# design.net
KiCad netlist of a schematic drawn in Altium Designer
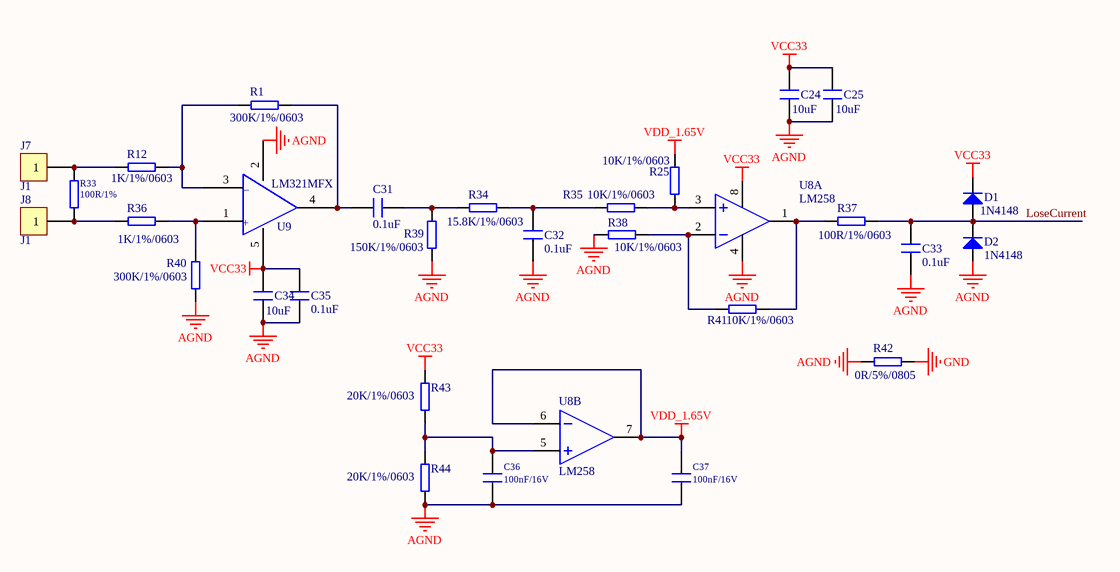
[diagram p0: 漏电流检测.SchDoc]

(export (version "E")
  (design (tool "Eeschema 10.0.6"))
  (components
    (comp (ref "C24") (value "10uF") (footprint "0603R") (libsource (lib "ES_Schematic") (part "CAP")))
    (comp (ref "C25") (value "10uF") (footprint "0603R") (libsource (lib "ES_Schematic") (part "CAP")))
    (comp (ref "C31") (value "0.1uF") (footprint "0603R") (libsource (lib "ES_Schematic") (part "CAP")))
    (comp (ref "C32") (value "0.1uF") (footprint "0603R") (libsource (lib "ES_Schematic") (part "CAP")))
    (comp (ref "C33") (value "0.1uF") (footprint "0603R") (libsource (lib "ES_Schematic") (part "CAP")))
    (comp (ref "C34") (value "10uF") (footprint "0603R") (libsource (lib "ES_Schematic") (part "CAP")))
    (comp (ref "C35") (value "0.1uF") (footprint "0603R") (libsource (lib "ES_Schematic") (part "CAP")))
    (comp (ref "C36") (value "100nF/16V") (footprint "0603R") (libsource (lib "ES_Schematic") (part "CAP")))
    (comp (ref "C37") (value "100nF/16V") (footprint "0603R") (libsource (lib "ES_Schematic") (part "CAP")))
    (comp (ref "D1") (value "1N4148") (footprint "1206D") (libsource (lib "ES_Schematic") (part "DIODE")))
    (comp (ref "D2") (value "1N4148") (footprint "1206D") (libsource (lib "ES_Schematic") (part "DIODE")))
    (comp (ref "J7") (value "J1") (footprint "贴片焊盘V1（3*2椭圆）") (libsource (lib "ES_Schematic") (part "J1")))
    (comp (ref "J8") (value "J1") (footprint "贴片焊盘V1（3*2椭圆）") (libsource (lib "ES_Schematic") (part "J1")))
    (comp (ref "R1") (value "300K/1%/0603") (footprint "0603r") (libsource (lib "ES_Schematic") (part "RES")))
    (comp (ref "R12") (value "1K/1%/0603") (footprint "0603r") (libsource (lib "ES_Schematic") (part "RES")))
    (comp (ref "R25") (value "10K/1%/0603") (footprint "0603r") (libsource (lib "ES_Schematic") (part "RES")))
    (comp (ref "R33") (value "100R/1%") (footprint "0805R") (libsource (lib "ES_Schematic") (part "RES")))
    (comp (ref "R34")
      (value "15.8K/1%/0603")
      (footprint "0603r")
      (libsource (lib "ES_Schematic") (part "RES"))
    )
    (comp (ref "R35") (value "10K/1%/0603") (footprint "0603r") (libsource (lib "ES_Schematic") (part "RES")))
    (comp (ref "R36") (value "1K/1%/0603") (footprint "0603r") (libsource (lib "ES_Schematic") (part "RES")))
    (comp (ref "R37")
      (value "100R/1%/0603")
      (footprint "0603r")
      (libsource (lib "ES_Schematic") (part "RES"))
    )
    (comp (ref "R38") (value "10K/1%/0603") (footprint "0603r") (libsource (lib "ES_Schematic") (part "RES")))
    (comp (ref "R39")
      (value "150K/1%/0603")
      (footprint "0603r")
      (libsource (lib "ES_Schematic") (part "RES"))
    )
    (comp (ref "R40")
      (value "300K/1%/0603")
      (footprint "0603r")
      (libsource (lib "ES_Schematic") (part "RES"))
    )
    (comp (ref "R41") (value "10K/1%/0603") (footprint "0603r") (libsource (lib "ES_Schematic") (part "RES")))
    (comp (ref "R42") (value "0R/5%/0805") (footprint "0805R") (libsource (lib "ES_Schematic") (part "RES")))
    (comp (ref "R43") (value "20K/1%/0603") (footprint "0603r") (libsource (lib "ES_Schematic") (part "RES")))
    (comp (ref "R44") (value "20K/1%/0603") (footprint "0603r") (libsource (lib "ES_Schematic") (part "RES")))
    (comp (ref "U8") (value "LM258") (footprint "SO8") (libsource (lib "sangjian") (part "LM358")))
    (comp (ref "U9")
      (value "LM321MFX")
      (footprint "SOT-23-5")
      (libsource (lib "ES_Schematic") (part "LM321MFX"))
    )
  )
  (nets
    (net (code "1") (name "/LoseCurrent") (class "Default")
      (node (ref "C33") (pin "1") (pinfunction "1_1") (pintype "passive"))
      (node (ref "D1") (pin "2") (pinfunction "A_2") (pintype "passive"))
      (node (ref "D2") (pin "1") (pinfunction "K_1") (pintype "passive"))
      (node (ref "R37") (pin "1") (pinfunction "1_1") (pintype "passive"))
    )
    (net (code "2") (name "AGND") (class "Default")
      (node (ref "C24") (pin "1") (pinfunction "1_1") (pintype "passive"))
      (node (ref "C25") (pin "1") (pinfunction "1_1") (pintype "passive"))
      (node (ref "C32") (pin "2") (pinfunction "2_2") (pintype "passive"))
      (node (ref "C33") (pin "2") (pinfunction "2_2") (pintype "passive"))
      (node (ref "C34") (pin "1") (pinfunction "1_1") (pintype "passive"))
      (node (ref "C35") (pin "1") (pinfunction "1_1") (pintype "passive"))
      (node (ref "C36") (pin "2") (pinfunction "2_2") (pintype "passive"))
      (node (ref "C37") (pin "2") (pinfunction "2_2") (pintype "passive"))
      (node (ref "D2") (pin "2") (pinfunction "A_2") (pintype "passive"))
      (node (ref "R38") (pin "2") (pinfunction "2_2") (pintype "passive"))
      (node (ref "R39") (pin "1") (pinfunction "1_1") (pintype "passive"))
      (node (ref "R40") (pin "1") (pinfunction "1_1") (pintype "passive"))
      (node (ref "R42") (pin "2") (pinfunction "2_2") (pintype "passive"))
      (node (ref "R44") (pin "2") (pinfunction "2_2") (pintype "passive"))
      (node (ref "U8") (pin "4") (pinfunction "4_4") (pintype "passive"))
      (node (ref "U9") (pin "2") (pintype "passive"))
    )
    (net (code "3") (name "GND") (class "Default")
      (node (ref "R42") (pin "1") (pinfunction "1_1") (pintype "passive"))
    )
    (net (code "4") (name "Net-(C31-Pad1)") (class "Default")
      (node (ref "C31") (pin "1") (pinfunction "1_1") (pintype "passive"))
      (node (ref "R34") (pin "2") (pinfunction "2_2") (pintype "passive"))
      (node (ref "R39") (pin "2") (pinfunction "2_2") (pintype "passive"))
    )
    (net (code "5") (name "Net-(C31-Pad2)") (class "Default")
      (node (ref "C31") (pin "2") (pinfunction "2_2") (pintype "passive"))
      (node (ref "R1") (pin "1") (pinfunction "1_1") (pintype "passive"))
      (node (ref "U9") (pin "4") (pintype "passive"))
    )
    (net (code "6") (name "Net-(C32-Pad1)") (class "Default")
      (node (ref "C32") (pin "1") (pinfunction "1_1") (pintype "passive"))
      (node (ref "R34") (pin "1") (pinfunction "1_1") (pintype "passive"))
      (node (ref "R35") (pin "2") (pinfunction "2_2") (pintype "passive"))
    )
    (net (code "7") (name "Net-(C36-Pad1)") (class "Default")
      (node (ref "C36") (pin "1") (pinfunction "1_1") (pintype "passive"))
      (node (ref "R43") (pin "2") (pinfunction "2_2") (pintype "passive"))
      (node (ref "R44") (pin "1") (pinfunction "1_1") (pintype "passive"))
      (node (ref "U8") (pin "5") (pinfunction "5_5") (pintype "passive"))
    )
    (net (code "8") (name "Net-(J7-Pad1)") (class "Default")
      (node (ref "J7") (pin "1") (pinfunction "1_1") (pintype "passive"))
      (node (ref "R12") (pin "1") (pinfunction "1_1") (pintype "passive"))
      (node (ref "R33") (pin "2") (pinfunction "2_2") (pintype "passive"))
    )
    (net (code "9") (name "Net-(J8-Pad1)") (class "Default")
      (node (ref "J8") (pin "1") (pinfunction "1_1") (pintype "passive"))
      (node (ref "R33") (pin "1") (pinfunction "1_1") (pintype "passive"))
      (node (ref "R36") (pin "2") (pinfunction "2_2") (pintype "passive"))
    )
    (net (code "10") (name "Net-(R1-Pad2)") (class "Default")
      (node (ref "R1") (pin "2") (pinfunction "2_2") (pintype "passive"))
      (node (ref "R12") (pin "2") (pinfunction "2_2") (pintype "passive"))
      (node (ref "U9") (pin "3") (pintype "passive"))
    )
    (net (code "11") (name "Net-(R25-Pad2)") (class "Default")
      (node (ref "R25") (pin "2") (pinfunction "2_2") (pintype "passive"))
      (node (ref "R35") (pin "1") (pinfunction "1_1") (pintype "passive"))
      (node (ref "U8") (pin "3") (pinfunction "3_3") (pintype "passive"))
    )
    (net (code "12") (name "Net-(R36-Pad1)") (class "Default")
      (node (ref "R36") (pin "1") (pinfunction "1_1") (pintype "passive"))
      (node (ref "R40") (pin "2") (pinfunction "2_2") (pintype "passive"))
      (node (ref "U9") (pin "1") (pintype "passive"))
    )
    (net (code "13") (name "Net-(R37-Pad2)") (class "Default")
      (node (ref "R37") (pin "2") (pinfunction "2_2") (pintype "passive"))
      (node (ref "R41") (pin "1") (pinfunction "1_1") (pintype "passive"))
      (node (ref "U8") (pin "1") (pinfunction "1_1") (pintype "passive"))
    )
    (net (code "14") (name "Net-(R38-Pad1)") (class "Default")
      (node (ref "R38") (pin "1") (pinfunction "1_1") (pintype "passive"))
      (node (ref "R41") (pin "2") (pinfunction "2_2") (pintype "passive"))
      (node (ref "U8") (pin "2") (pinfunction "2_2") (pintype "passive"))
    )
    (net (code "15") (name "VCC33") (class "Default")
      (node (ref "C24") (pin "2") (pinfunction "2_2") (pintype "passive"))
      (node (ref "C25") (pin "2") (pinfunction "2_2") (pintype "passive"))
      (node (ref "C34") (pin "2") (pinfunction "2_2") (pintype "passive"))
      (node (ref "C35") (pin "2") (pinfunction "2_2") (pintype "passive"))
      (node (ref "D1") (pin "1") (pinfunction "K_1") (pintype "passive"))
      (node (ref "R43") (pin "1") (pinfunction "1_1") (pintype "passive"))
      (node (ref "U8") (pin "8") (pinfunction "8_8") (pintype "passive"))
      (node (ref "U9") (pin "5") (pintype "passive"))
    )
    (net (code "16") (name "VDD_1.65V") (class "Default")
      (node (ref "C37") (pin "1") (pinfunction "1_1") (pintype "passive"))
      (node (ref "R25") (pin "1") (pinfunction "1_1") (pintype "passive"))
      (node (ref "U8") (pin "6") (pinfunction "6_6") (pintype "passive"))
      (node (ref "U8") (pin "7") (pinfunction "7_7") (pintype "passive"))
    )
  )
)
